# ESP-shild-1_0.net
KiCad netlist of a schematic drawn in EAGLE
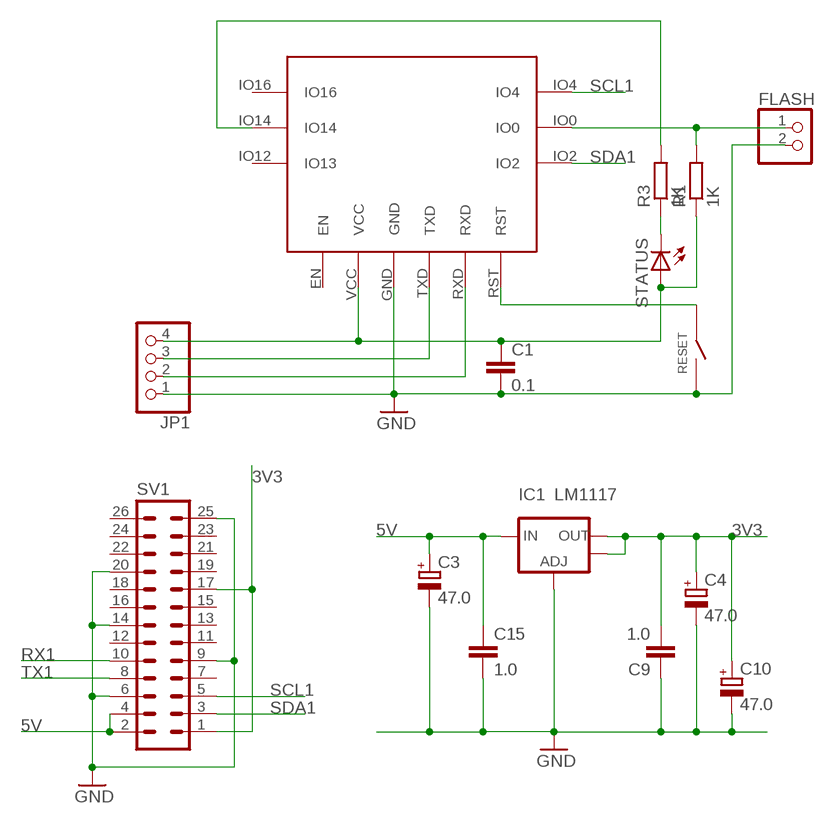
[diagram p0: schematic, sheet 1]

(export (version "E")
  (design (tool "Eeschema 10.0.6"))
  (components
    (comp (ref "C1")
      (value "0.1")
      (footprint "eagle-import:C0805")
      (libsource (lib "eagle-import") (part "C-EUC0805"))
    )
    (comp (ref "C3")
      (value "47.0")
      (footprint "eagle-import:SMC_D")
      (libsource (lib "eagle-import") (part "CPOL-EUSMCD"))
    )
    (comp (ref "C4")
      (value "47.0")
      (footprint "eagle-import:SMC_B")
      (libsource (lib "eagle-import") (part "CPOL-EUSMCB"))
    )
    (comp (ref "C9")
      (value "1.0")
      (footprint "eagle-import:C0805")
      (libsource (lib "eagle-import") (part "C-EUC0805"))
    )
    (comp (ref "C10")
      (value "47.0")
      (footprint "eagle-import:SMC_D")
      (libsource (lib "eagle-import") (part "CPOL-EUSMCD"))
    )
    (comp (ref "C15")
      (value "1.0")
      (footprint "eagle-import:C0805")
      (libsource (lib "eagle-import") (part "C-EUC0805"))
    )
    (comp (ref "ESP-M3")
      (value "ESP-M3")
      (footprint "eagle-import:ESP-M3")
      (libsource (lib "eagle-import") (part "ESP-M3"))
    )
    (comp (ref "FLASH")
      (value "PINHD-1X2/90")
      (footprint "eagle-import:1X02_90")
      (libsource (lib "eagle-import") (part "PINHD-1X2/90"))
    )
    (comp (ref "IC1")
      (value "LM1117")
      (footprint "eagle-import:SOT223")
      (libsource (lib "eagle-import") (part "V_REG_LM1117SOT223"))
    )
    (comp (ref "JP1")
      (value "PINHD-1X4/90")
      (footprint "eagle-import:1X04_90")
      (libsource (lib "eagle-import") (part "PINHD-1X4/90"))
    )
    (comp (ref "R1")
      (value "1K")
      (footprint "eagle-import:R0603")
      (libsource (lib "eagle-import") (part "R-EU_R0603"))
    )
    (comp (ref "R3")
      (value "1K")
      (footprint "eagle-import:R0603")
      (libsource (lib "eagle-import") (part "R-EU_R0603"))
    )
    (comp (ref "RESET")
      (value "TACT3X4")
      (footprint "eagle-import:TACT3X4")
      (libsource (lib "eagle-import") (part "TACT3X4"))
    )
    (comp (ref "STATUS")
      (value "LEDSML1206")
      (footprint "eagle-import:SML1206")
      (libsource (lib "eagle-import") (part "LEDSML1206"))
    )
    (comp (ref "SV1")
      (value "MA13-2")
      (footprint "eagle-import:MA13-2")
      (libsource (lib "eagle-import") (part "MA13-2"))
    )
  )
  (nets
    (net (code "1") (name "/3V3") (class "Default")
      (node (ref "C1") (pin "1") (pinfunction "1_1") (pintype "passive"))
      (node (ref "C10") (pin "+") (pinfunction "+_+") (pintype "passive"))
      (node (ref "C4") (pin "+") (pinfunction "+_+") (pintype "passive"))
      (node (ref "C9") (pin "2") (pinfunction "2_2") (pintype "passive"))
      (node (ref "ESP-M3") (pin "VCC") (pinfunction "VCC_VCC") (pintype "bidirectional"))
      (node (ref "IC1") (pin "2") (pinfunction "OUT_2") (pintype "output"))
      (node (ref "IC1") (pin "4") (pinfunction "OUT_4") (pintype "output"))
      (node (ref "JP1") (pin "4") (pinfunction "4_4") (pintype "passive"))
      (node (ref "R1") (pin "1") (pinfunction "1_1") (pintype "passive"))
      (node (ref "STATUS") (pin "A") (pinfunction "A_A") (pintype "passive"))
      (node (ref "SV1") (pin "1") (pinfunction "1_1") (pintype "passive"))
      (node (ref "SV1") (pin "17") (pinfunction "17_17") (pintype "passive"))
    )
    (net (code "2") (name "/5V") (class "Default")
      (node (ref "C15") (pin "1") (pinfunction "1_1") (pintype "passive"))
      (node (ref "C3") (pin "+") (pinfunction "+_+") (pintype "passive"))
      (node (ref "IC1") (pin "3") (pinfunction "IN_3") (pintype "input"))
      (node (ref "SV1") (pin "2") (pinfunction "2_2") (pintype "passive"))
      (node (ref "SV1") (pin "4") (pinfunction "4_4") (pintype "passive"))
    )
    (net (code "3") (name "/RX1") (class "Default")
      (node (ref "ESP-M3") (pin "RXD") (pinfunction "RXD_RXD") (pintype "bidirectional"))
      (node (ref "JP1") (pin "2") (pinfunction "2_2") (pintype "passive"))
      (node (ref "SV1") (pin "10") (pinfunction "10_10") (pintype "passive"))
    )
    (net (code "4") (name "/SCL1") (class "Default")
      (node (ref "ESP-M3") (pin "IO4") (pinfunction "IO4_IO4") (pintype "bidirectional"))
      (node (ref "SV1") (pin "5") (pinfunction "5_5") (pintype "passive"))
    )
    (net (code "5") (name "/SDA1") (class "Default")
      (node (ref "ESP-M3") (pin "IO2") (pinfunction "IO2_IO2") (pintype "bidirectional"))
      (node (ref "SV1") (pin "3") (pinfunction "3_3") (pintype "passive"))
    )
    (net (code "6") (name "/TX1") (class "Default")
      (node (ref "ESP-M3") (pin "TXD") (pinfunction "TXD_TXD") (pintype "bidirectional"))
      (node (ref "JP1") (pin "3") (pinfunction "3_3") (pintype "passive"))
      (node (ref "SV1") (pin "8") (pinfunction "8_8") (pintype "passive"))
    )
    (net (code "7") (name "GND") (class "Default")
      (node (ref "C1") (pin "2") (pinfunction "2_2") (pintype "passive"))
      (node (ref "C10") (pin "-") (pinfunction "-_-") (pintype "passive"))
      (node (ref "C15") (pin "2") (pinfunction "2_2") (pintype "passive"))
      (node (ref "C3") (pin "-") (pinfunction "-_-") (pintype "passive"))
      (node (ref "C4") (pin "-") (pinfunction "-_-") (pintype "passive"))
      (node (ref "C9") (pin "1") (pinfunction "1_1") (pintype "passive"))
      (node (ref "ESP-M3") (pin "GND") (pinfunction "GND_GND") (pintype "bidirectional"))
      (node (ref "FLASH") (pin "2") (pinfunction "2_2") (pintype "passive"))
      (node (ref "IC1") (pin "1") (pinfunction "ADJ_1") (pintype "input"))
      (node (ref "JP1") (pin "1") (pinfunction "1_1") (pintype "passive"))
      (node (ref "RESET") (pin "P$2") (pinfunction "P$2_P$2") (pintype "bidirectional"))
      (node (ref "SV1") (pin "14") (pinfunction "14_14") (pintype "passive"))
      (node (ref "SV1") (pin "20") (pinfunction "20_20") (pintype "passive"))
      (node (ref "SV1") (pin "25") (pinfunction "25_25") (pintype "passive"))
      (node (ref "SV1") (pin "6") (pinfunction "6_6") (pintype "passive"))
      (node (ref "SV1") (pin "9") (pinfunction "9_9") (pintype "passive"))
    )
    (net (code "8") (name "Net-(ESP-M3-PadIO0)") (class "Default")
      (node (ref "ESP-M3") (pin "IO0") (pinfunction "IO0_IO0") (pintype "bidirectional"))
      (node (ref "FLASH") (pin "1") (pinfunction "1_1") (pintype "passive"))
      (node (ref "R1") (pin "2") (pinfunction "2_2") (pintype "passive"))
    )
    (net (code "9") (name "Net-(ESP-M3-PadIO14)") (class "Default")
      (node (ref "ESP-M3") (pin "IO14") (pinfunction "IO14_IO14") (pintype "bidirectional"))
      (node (ref "R3") (pin "2") (pinfunction "2_2") (pintype "passive"))
    )
    (net (code "10") (name "Net-(ESP-M3-PadRST)") (class "Default")
      (node (ref "ESP-M3") (pin "RST") (pinfunction "RST_RST") (pintype "bidirectional"))
      (node (ref "RESET") (pin "P$1") (pinfunction "P$1_P$1") (pintype "bidirectional"))
    )
    (net (code "11") (name "Net-(R3-Pad1)") (class "Default")
      (node (ref "R3") (pin "1") (pinfunction "1_1") (pintype "passive"))
      (node (ref "STATUS") (pin "C") (pinfunction "C_C") (pintype "passive"))
    )
    (net (code "12") (name "unconnected-(ESP-M3-IO13-PadIO12)") (class "Default")
      (node (ref "ESP-M3") (pin "IO12") (pinfunction "IO13_IO12") (pintype "bidirectional"))
    )
    (net (code "13") (name "unconnected-(ESP-M3-PadEN)") (class "Default")
      (node (ref "ESP-M3") (pin "EN") (pinfunction "EN_EN") (pintype "bidirectional"))
    )
    (net (code "14") (name "unconnected-(ESP-M3-PadIO16)") (class "Default")
      (node (ref "ESP-M3") (pin "IO16") (pinfunction "IO16_IO16") (pintype "bidirectional"))
    )
    (net (code "15") (name "unconnected-(SV1-Pad7)") (class "Default")
      (node (ref "SV1") (pin "7") (pinfunction "7_7") (pintype "passive"))
    )
    (net (code "16") (name "unconnected-(SV1-Pad11)") (class "Default")
      (node (ref "SV1") (pin "11") (pinfunction "11_11") (pintype "passive"))
    )
    (net (code "17") (name "unconnected-(SV1-Pad12)") (class "Default")
      (node (ref "SV1") (pin "12") (pinfunction "12_12") (pintype "passive"))
    )
    (net (code "18") (name "unconnected-(SV1-Pad13)") (class "Default")
      (node (ref "SV1") (pin "13") (pinfunction "13_13") (pintype "passive"))
    )
    (net (code "19") (name "unconnected-(SV1-Pad15)") (class "Default")
      (node (ref "SV1") (pin "15") (pinfunction "15_15") (pintype "passive"))
    )
    (net (code "20") (name "unconnected-(SV1-Pad16)") (class "Default")
      (node (ref "SV1") (pin "16") (pinfunction "16_16") (pintype "passive"))
    )
    (net (code "21") (name "unconnected-(SV1-Pad18)") (class "Default")
      (node (ref "SV1") (pin "18") (pinfunction "18_18") (pintype "passive"))
    )
    (net (code "22") (name "unconnected-(SV1-Pad19)") (class "Default")
      (node (ref "SV1") (pin "19") (pinfunction "19_19") (pintype "passive"))
    )
    (net (code "23") (name "unconnected-(SV1-Pad21)") (class "Default")
      (node (ref "SV1") (pin "21") (pinfunction "21_21") (pintype "passive"))
    )
    (net (code "24") (name "unconnected-(SV1-Pad22)") (class "Default")
      (node (ref "SV1") (pin "22") (pinfunction "22_22") (pintype "passive"))
    )
    (net (code "25") (name "unconnected-(SV1-Pad23)") (class "Default")
      (node (ref "SV1") (pin "23") (pinfunction "23_23") (pintype "passive"))
    )
    (net (code "26") (name "unconnected-(SV1-Pad24)") (class "Default")
      (node (ref "SV1") (pin "24") (pinfunction "24_24") (pintype "passive"))
    )
    (net (code "27") (name "unconnected-(SV1-Pad26)") (class "Default")
      (node (ref "SV1") (pin "26") (pinfunction "26_26") (pintype "passive"))
    )
  )
)
